# UserOutput.net
KiCad netlist of a schematic drawn in Altium Designer
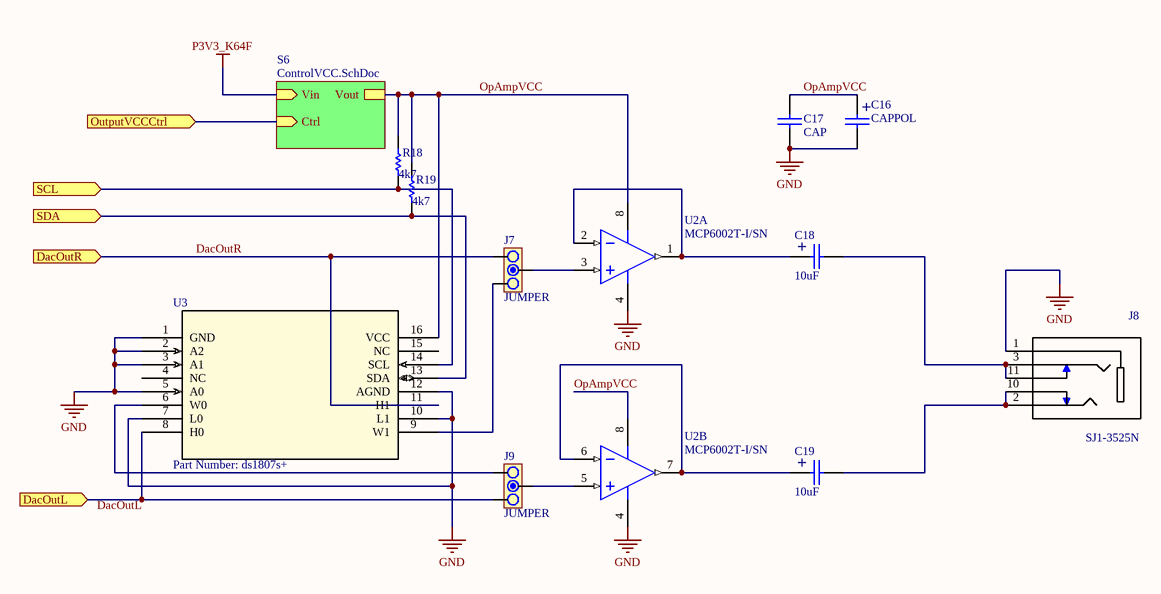
[diagram p0: UserOutput.SchDoc]

(export (version "E")
  (design (tool "Eeschema 10.0.6"))
  (components
    (comp (ref "C16") (value "CAPPOL") (footprint "CAP100RP") (libsource (lib "LIBEBAL") (part "CAPPOL")))
    (comp (ref "C17") (value "CAP") (footprint "0805") (libsource (lib "LIBEBAL") (part "CAP")))
    (comp (ref "C18") (value "10uF") (footprint "CAP100RP") (libsource (lib "LIBEBAL") (part "CAPPOL")))
    (comp (ref "C19") (value "10uF") (footprint "CAP100RP") (libsource (lib "LIBEBAL") (part "CAPPOL")))
    (comp (ref "J7") (value "JUMPER") (footprint "JUMPER3") (libsource (lib "LIBEBAL") (part "JUMPER3")))
    (comp (ref "J8")
      (value "SJ1-3525N")
      (footprint "*CUI_SJ1-3525N")
      (libsource (lib "SJ1-3525N") (part "SJ1-3525N"))
    )
    (comp (ref "J9") (value "JUMPER") (footprint "JUMPER3") (libsource (lib "LIBEBAL") (part "JUMPER3")))
    (comp (ref "R18") (value "4k7") (footprint "0805") (libsource (lib "LIBEBAL") (part "RES")))
    (comp (ref "R19") (value "4k7") (footprint "0805") (libsource (lib "LIBEBAL") (part "RES")))
    (comp (ref "U2")
      (value "MCP6002T-I/SN")
      (footprint "SOIC-SN8_N")
      (description "1 MHz, Low-Power Operational Amplifier, 8-Pin SOIC, Industrial Temperature, Tape and Reel")
      (fields (field (name "PUBLISHER") "Altium Limited"))
      (libsource (lib "Microchip Linear Devices") (part "MCP6002T-I/SN"))
    )
    (comp (ref "U3")
      (value "Part Number: ds1807s+")
      (footprint "21-0042B_16")
      (description "No Description Available")
      (fields
        (field (name "MANUFACTURER_PART_NUMBER") "ds1807s+")
        (field (name "COPYRIGHT") "Copyright (C) 2018 Accelerated Designs. All rights reserved")
      )
      (libsource (lib "PoteDigital") (part "ds1807s+"))
    )
  )
  (nets
    (net (code "1") (name "/DacOutL") (class "Default")
      (node (ref "J9") (pin "1") (pinfunction "1_1") (pintype "passive"))
      (node (ref "U3") (pin "8") (pinfunction "H0_8") (pintype "passive"))
    )
    (net (code "2") (name "/DacOutR") (class "Default")
      (node (ref "J7") (pin "3") (pinfunction "3_3") (pintype "passive"))
      (node (ref "U3") (pin "11") (pinfunction "H1_11") (pintype "passive"))
    )
    (net (code "3") (name "/OpAmpVCC") (class "Default")
      (node (ref "C16") (pin "1") (pinfunction "1_1") (pintype "passive"))
      (node (ref "C17") (pin "1") (pinfunction "1_1") (pintype "passive"))
      (node (ref "R18") (pin "2") (pinfunction "2_2") (pintype "passive"))
      (node (ref "R19") (pin "2") (pinfunction "2_2") (pintype "passive"))
      (node (ref "U2") (pin "8") (pinfunction "VDD_8") (pintype "power_in"))
      (node (ref "U3") (pin "16") (pinfunction "VCC_16") (pintype "power_in"))
    )
    (net (code "5") (name "/SCL") (class "Default")
      (node (ref "R18") (pin "1") (pinfunction "1_1") (pintype "passive"))
      (node (ref "U3") (pin "14") (pinfunction "SCL_14") (pintype "input"))
    )
    (net (code "6") (name "/SDA") (class "Default")
      (node (ref "R19") (pin "1") (pinfunction "1_1") (pintype "passive"))
      (node (ref "U3") (pin "13") (pinfunction "SDA_13") (pintype "bidirectional"))
    )
    (net (code "7") (name "GND") (class "Default")
      (node (ref "C16") (pin "2") (pinfunction "2_2") (pintype "passive"))
      (node (ref "C17") (pin "2") (pinfunction "2_2") (pintype "passive"))
      (node (ref "J8") (pin "1") (pinfunction "1_1") (pintype "passive"))
      (node (ref "U2") (pin "4") (pinfunction "VSS_4") (pintype "power_in"))
      (node (ref "U3") (pin "1") (pinfunction "GND_1") (pintype "power_in"))
      (node (ref "U3") (pin "10") (pinfunction "L1_10") (pintype "passive"))
      (node (ref "U3") (pin "12") (pinfunction "AGND_12") (pintype "power_in"))
      (node (ref "U3") (pin "2") (pinfunction "A2_2") (pintype "input"))
      (node (ref "U3") (pin "3") (pinfunction "A1_3") (pintype "input"))
      (node (ref "U3") (pin "5") (pinfunction "A0_5") (pintype "input"))
      (node (ref "U3") (pin "7") (pinfunction "L0_7") (pintype "passive"))
    )
    (net (code "8") (name "Net-(C18-Pad2)") (class "Default")
      (node (ref "C18") (pin "2") (pinfunction "2_2") (pintype "passive"))
      (node (ref "J8") (pin "11") (pinfunction "11_11") (pintype "passive"))
      (node (ref "J8") (pin "3") (pinfunction "3_3") (pintype "passive"))
    )
    (net (code "9") (name "Net-(C19-Pad2)") (class "Default")
      (node (ref "C19") (pin "2") (pinfunction "2_2") (pintype "passive"))
      (node (ref "J8") (pin "10") (pinfunction "10_10") (pintype "passive"))
      (node (ref "J8") (pin "2") (pinfunction "2_2") (pintype "passive"))
    )
    (net (code "10") (name "Net-(U2A-VINA+)") (class "Default")
      (node (ref "J7") (pin "2") (pinfunction "2_2") (pintype "passive"))
      (node (ref "U2") (pin "3") (pinfunction "VINA+_3") (pintype "input"))
    )
    (net (code "11") (name "Net-(U2A-VINA-)") (class "Default")
      (node (ref "C18") (pin "1") (pinfunction "1_1") (pintype "passive"))
      (node (ref "U2") (pin "1") (pinfunction "VOUTA_1") (pintype "output"))
      (node (ref "U2") (pin "2") (pinfunction "VINA-_2") (pintype "input"))
    )
    (net (code "12") (name "Net-(U2B-VINB+)") (class "Default")
      (node (ref "J9") (pin "2") (pinfunction "2_2") (pintype "passive"))
      (node (ref "U2") (pin "5") (pinfunction "VINB+_5") (pintype "input"))
    )
    (net (code "13") (name "Net-(U2B-VINB-)") (class "Default")
      (node (ref "C19") (pin "1") (pinfunction "1_1") (pintype "passive"))
      (node (ref "U2") (pin "6") (pinfunction "VINB-_6") (pintype "input"))
      (node (ref "U2") (pin "7") (pinfunction "VOUTB_7") (pintype "output"))
    )
    (net (code "14") (name "Net-(U3-W0)") (class "Default")
      (node (ref "J9") (pin "3") (pinfunction "3_3") (pintype "passive"))
      (node (ref "U3") (pin "6") (pinfunction "W0_6") (pintype "passive"))
    )
    (net (code "15") (name "Net-(U3-W1)") (class "Default")
      (node (ref "J7") (pin "1") (pinfunction "1_1") (pintype "passive"))
      (node (ref "U3") (pin "9") (pinfunction "W1_9") (pintype "passive"))
    )
    (net (code "17") (name "unconnected-(U3-NC-Pad4)") (class "Default")
      (node (ref "U3") (pin "4") (pinfunction "NC_4") (pintype "passive"))
    )
    (net (code "18") (name "unconnected-(U3-NC-Pad15)") (class "Default")
      (node (ref "U3") (pin "15") (pinfunction "NC_15") (pintype "passive"))
    )
  )
)
